# ambisoniqueAlim.net
KiCad netlist of a schematic drawn in EAGLE
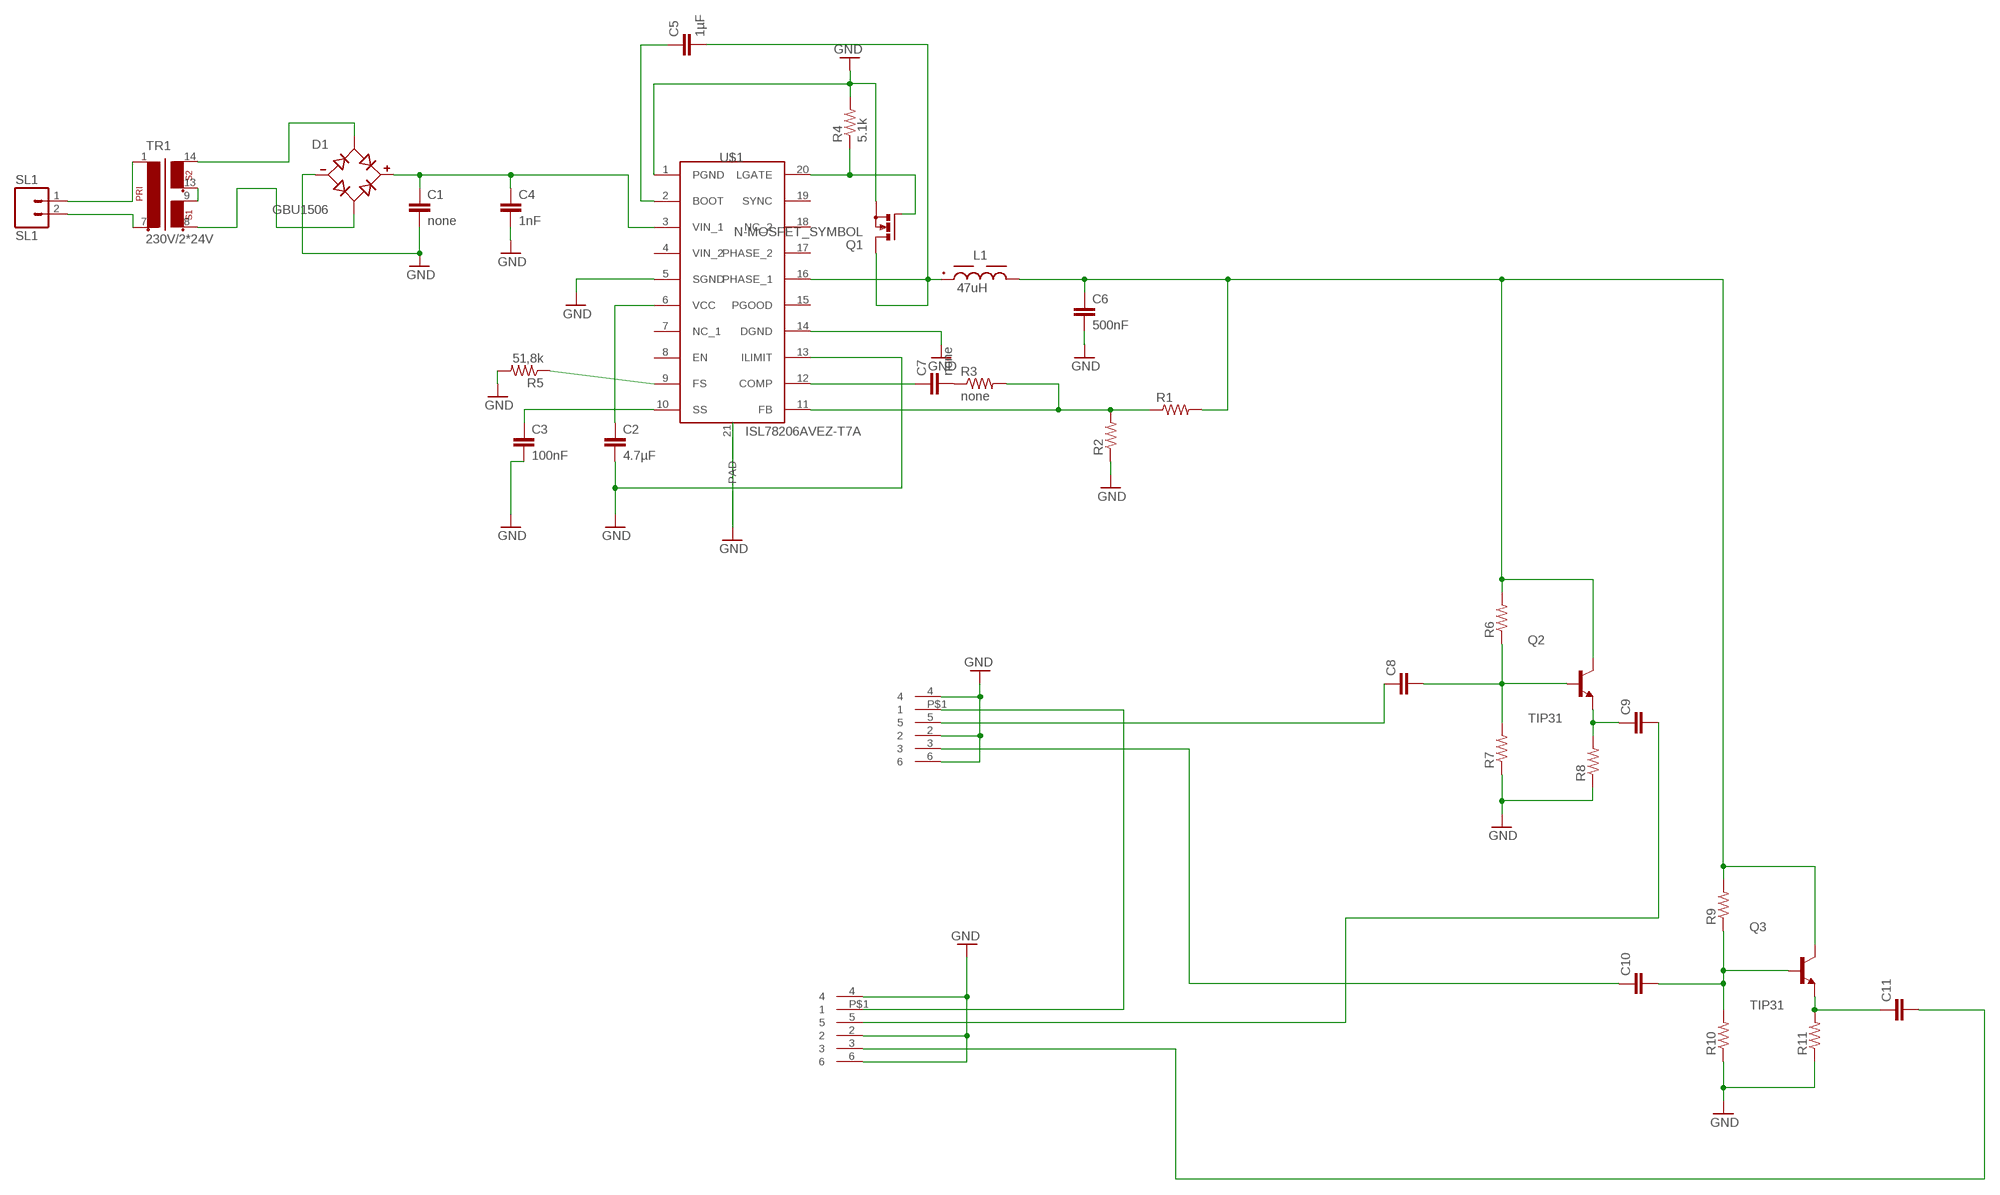
[diagram p0: schematic, sheet 1]

(export (version "E")
  (design (tool "Eeschema 10.0.6"))
  (components
    (comp (ref "C1")
      (value "none")
      (footprint "eagle-import:C0603")
      (libsource (lib "eagle-import") (part "C-EUC0603"))
    )
    (comp (ref "C2")
      (value "4.7µF")
      (footprint "eagle-import:C0603")
      (libsource (lib "eagle-import") (part "C-EUC0603"))
    )
    (comp (ref "C3")
      (value "100nF")
      (footprint "eagle-import:C0603")
      (libsource (lib "eagle-import") (part "C-EUC0603"))
    )
    (comp (ref "C4")
      (value "1nF")
      (footprint "eagle-import:C0603")
      (libsource (lib "eagle-import") (part "C-EUC0603"))
    )
    (comp (ref "C5")
      (value "1µF")
      (footprint "eagle-import:C0603")
      (libsource (lib "eagle-import") (part "C-EUC0603"))
    )
    (comp (ref "C6")
      (value "500nF")
      (footprint "eagle-import:C0603")
      (libsource (lib "eagle-import") (part "C-EUC0603"))
    )
    (comp (ref "C7")
      (value "none")
      (footprint "eagle-import:C0603")
      (libsource (lib "eagle-import") (part "C-EUC0603"))
    )
    (comp (ref "C8")
      (value "C-EUC0603")
      (footprint "eagle-import:C0603")
      (libsource (lib "eagle-import") (part "C-EUC0603"))
    )
    (comp (ref "C9")
      (value "C-EUC0603")
      (footprint "eagle-import:C0603")
      (libsource (lib "eagle-import") (part "C-EUC0603"))
    )
    (comp (ref "C10")
      (value "C-EUC0603")
      (footprint "eagle-import:C0603")
      (libsource (lib "eagle-import") (part "C-EUC0603"))
    )
    (comp (ref "C11")
      (value "C-EUC0603")
      (footprint "eagle-import:C0603")
      (libsource (lib "eagle-import") (part "C-EUC0603"))
    )
    (comp (ref "D1")
      (value "GBU1506")
      (footprint "eagle-import:SIP343W114P508L2205H2134Q4")
      (fields (field (name "MF") "Taiwan Semiconductor Corporation"))
      (libsource (lib "eagle-import") (part "GBU1506"))
    )
    (comp (ref "L1")
      (value "47uH")
      (footprint "eagle-import:WE-PDA_1210")
      (libsource (lib "eagle-import") (part "WE-PDA_1210_7847709470"))
    )
    (comp (ref "Q2")
      (value "TIP31")
      (footprint "eagle-import:TO254P1060X482X2222-3")
      (fields (field (name "MF") "ON"))
      (libsource (lib "eagle-import") (part "TIP31"))
    )
    (comp (ref "Q3")
      (value "TIP31")
      (footprint "eagle-import:TO254P1060X482X2222-3")
      (fields (field (name "MF") "ON"))
      (libsource (lib "eagle-import") (part "TIP31"))
    )
    (comp (ref "R1")
      (value "R-US_R0603")
      (footprint "eagle-import:R0603")
      (libsource (lib "eagle-import") (part "R-US_R0603"))
    )
    (comp (ref "R2")
      (value "R-US_R0603")
      (footprint "eagle-import:R0603")
      (libsource (lib "eagle-import") (part "R-US_R0603"))
    )
    (comp (ref "R3")
      (value "none")
      (footprint "eagle-import:R0603")
      (libsource (lib "eagle-import") (part "R-US_R0603"))
    )
    (comp (ref "R4")
      (value "5.1k")
      (footprint "eagle-import:R0603")
      (libsource (lib "eagle-import") (part "R-US_R0603"))
    )
    (comp (ref "R5")
      (value "51,8k")
      (footprint "eagle-import:R0603")
      (libsource (lib "eagle-import") (part "R-US_R0603"))
    )
    (comp (ref "R6")
      (value "R-US_R0603")
      (footprint "eagle-import:R0603")
      (libsource (lib "eagle-import") (part "R-US_R0603"))
    )
    (comp (ref "R7")
      (value "R-US_R0603")
      (footprint "eagle-import:R0603")
      (libsource (lib "eagle-import") (part "R-US_R0603"))
    )
    (comp (ref "R8")
      (value "R-US_R0603")
      (footprint "eagle-import:R0603")
      (libsource (lib "eagle-import") (part "R-US_R0603"))
    )
    (comp (ref "R9")
      (value "R-US_R0603")
      (footprint "eagle-import:R0603")
      (libsource (lib "eagle-import") (part "R-US_R0603"))
    )
    (comp (ref "R10")
      (value "R-US_R0603")
      (footprint "eagle-import:R0603")
      (libsource (lib "eagle-import") (part "R-US_R0603"))
    )
    (comp (ref "R11")
      (value "R-US_R0603")
      (footprint "eagle-import:R0603")
      (libsource (lib "eagle-import") (part "R-US_R0603"))
    )
    (comp (ref "SL1")
      (value "SL1")
      (footprint "eagle-import:02P")
      (libsource (lib "eagle-import") (part "M02"))
    )
    (comp (ref "TR1")
      (value "230V/2*24V")
      (footprint "eagle-import:EI60-2")
      (libsource (lib "eagle-import") (part "EI60-2"))
    )
    (comp (ref "U$1")
      (value "ISL78206AVEZ-T7A")
      (footprint "eagle-import:SOP65P640X110-21N")
      (libsource (lib "eagle-import") (part "ISL78206AVEZ-T7A"))
    )
    (comp (ref "U$2")
      (value "JACK6.35MMRSPRODEV")
      (footprint "eagle-import:JACKRSPRO6.35MM")
      (libsource (lib "eagle-import") (part "JACK6.35MMRSPRODEV"))
    )
    (comp (ref "U$3")
      (value "JACK6.35MMRSPRODEV")
      (footprint "eagle-import:JACKRSPRO6.35MM")
      (libsource (lib "eagle-import") (part "JACK6.35MMRSPRODEV"))
    )
  )
  (nets
    (net (code "1") (name "GND") (class "Default")
      (node (ref "C1") (pin "2") (pinfunction "2_2") (pintype "passive"))
      (node (ref "C2") (pin "2") (pinfunction "2_2") (pintype "passive"))
      (node (ref "C3") (pin "2") (pinfunction "2_2") (pintype "passive"))
      (node (ref "C4") (pin "2") (pinfunction "2_2") (pintype "passive"))
      (node (ref "C6") (pin "2") (pinfunction "2_2") (pintype "passive"))
      (node (ref "D1") (pin "-") (pinfunction "-_-") (pintype "passive"))
      (node (ref "R10") (pin "1") (pinfunction "1_1") (pintype "passive"))
      (node (ref "R11") (pin "1") (pinfunction "1_1") (pintype "passive"))
      (node (ref "R2") (pin "1") (pinfunction "1_1") (pintype "passive"))
      (node (ref "R4") (pin "2") (pinfunction "2_2") (pintype "passive"))
      (node (ref "R5") (pin "2") (pinfunction "2_2") (pintype "passive"))
      (node (ref "R7") (pin "1") (pinfunction "1_1") (pintype "passive"))
      (node (ref "R8") (pin "1") (pinfunction "1_1") (pintype "passive"))
      (node (ref "U$1") (pin "1") (pinfunction "PGND_1") (pintype "bidirectional"))
      (node (ref "U$1") (pin "13") (pinfunction "ILIMIT_13") (pintype "bidirectional"))
      (node (ref "U$1") (pin "14") (pinfunction "DGND_14") (pintype "bidirectional"))
      (node (ref "U$1") (pin "21") (pinfunction "PAD_21") (pintype "bidirectional"))
      (node (ref "U$1") (pin "5") (pinfunction "SGND_5") (pintype "bidirectional"))
      (node (ref "U$2") (pin "2") (pinfunction "2_2") (pintype "bidirectional"))
      (node (ref "U$2") (pin "4") (pinfunction "4_4") (pintype "bidirectional"))
      (node (ref "U$2") (pin "6") (pinfunction "6_6") (pintype "bidirectional"))
      (node (ref "U$3") (pin "2") (pinfunction "2_2") (pintype "bidirectional"))
      (node (ref "U$3") (pin "4") (pinfunction "4_4") (pintype "bidirectional"))
      (node (ref "U$3") (pin "6") (pinfunction "6_6") (pintype "bidirectional"))
    )
    (net (code "2") (name "Net-(C7-Pad2)") (class "Default")
      (node (ref "C7") (pin "2") (pinfunction "2_2") (pintype "passive"))
      (node (ref "R3") (pin "1") (pinfunction "1_1") (pintype "passive"))
    )
    (net (code "3") (name "Net-(C8-Pad1)") (class "Default")
      (node (ref "C8") (pin "1") (pinfunction "1_1") (pintype "passive"))
      (node (ref "U$2") (pin "5") (pinfunction "5_5") (pintype "bidirectional"))
    )
    (net (code "4") (name "Net-(C9-Pad2)") (class "Default")
      (node (ref "C9") (pin "2") (pinfunction "2_2") (pintype "passive"))
      (node (ref "U$3") (pin "5") (pinfunction "5_5") (pintype "bidirectional"))
    )
    (net (code "5") (name "Net-(C10-Pad1)") (class "Default")
      (node (ref "C10") (pin "1") (pinfunction "1_1") (pintype "passive"))
      (node (ref "U$2") (pin "3") (pinfunction "3_3") (pintype "bidirectional"))
    )
    (net (code "6") (name "Net-(C11-Pad2)") (class "Default")
      (node (ref "C11") (pin "2") (pinfunction "2_2") (pintype "passive"))
      (node (ref "U$3") (pin "3") (pinfunction "3_3") (pintype "bidirectional"))
    )
    (net (code "7") (name "Net-(Q2-B)") (class "Default")
      (node (ref "C8") (pin "2") (pinfunction "2_2") (pintype "passive"))
      (node (ref "Q2") (pin "1") (pinfunction "B_1") (pintype "passive"))
      (node (ref "R6") (pin "1") (pinfunction "1_1") (pintype "passive"))
      (node (ref "R7") (pin "2") (pinfunction "2_2") (pintype "passive"))
    )
    (net (code "8") (name "Net-(Q2-C)") (class "Default")
      (node (ref "C6") (pin "1") (pinfunction "1_1") (pintype "passive"))
      (node (ref "L1") (pin "2") (pinfunction "2_2") (pintype "passive"))
      (node (ref "Q2") (pin "2") (pinfunction "C_2") (pintype "passive"))
      (node (ref "Q3") (pin "2") (pinfunction "C_2") (pintype "passive"))
      (node (ref "R1") (pin "2") (pinfunction "2_2") (pintype "passive"))
      (node (ref "R6") (pin "2") (pinfunction "2_2") (pintype "passive"))
      (node (ref "R9") (pin "2") (pinfunction "2_2") (pintype "passive"))
    )
    (net (code "9") (name "Net-(Q2-E)") (class "Default")
      (node (ref "C9") (pin "1") (pinfunction "1_1") (pintype "passive"))
      (node (ref "Q2") (pin "3") (pinfunction "E_3") (pintype "passive"))
      (node (ref "R8") (pin "2") (pinfunction "2_2") (pintype "passive"))
    )
    (net (code "10") (name "Net-(Q3-B)") (class "Default")
      (node (ref "C10") (pin "2") (pinfunction "2_2") (pintype "passive"))
      (node (ref "Q3") (pin "1") (pinfunction "B_1") (pintype "passive"))
      (node (ref "R10") (pin "2") (pinfunction "2_2") (pintype "passive"))
      (node (ref "R9") (pin "1") (pinfunction "1_1") (pintype "passive"))
    )
    (net (code "11") (name "Net-(Q3-E)") (class "Default")
      (node (ref "C11") (pin "1") (pinfunction "1_1") (pintype "passive"))
      (node (ref "Q3") (pin "3") (pinfunction "E_3") (pintype "passive"))
      (node (ref "R11") (pin "2") (pinfunction "2_2") (pintype "passive"))
    )
    (net (code "12") (name "Net-(SL1-Pad1)") (class "Default")
      (node (ref "SL1") (pin "1") (pinfunction "1_1") (pintype "passive"))
      (node (ref "TR1") (pin "1") (pinfunction "1_1") (pintype "passive"))
    )
    (net (code "13") (name "Net-(TR1-2)") (class "Default")
      (node (ref "SL1") (pin "2") (pinfunction "2_2") (pintype "passive"))
      (node (ref "TR1") (pin "7") (pinfunction "2_7") (pintype "passive"))
    )
    (net (code "14") (name "Net-(TR1-3)") (class "Default")
      (node (ref "D1") (pin "AC2") (pinfunction "AC2_AC2") (pintype "passive"))
      (node (ref "TR1") (pin "8") (pinfunction "3_8") (pintype "passive"))
    )
    (net (code "15") (name "Net-(TR1-4)") (class "Default")
      (node (ref "TR1") (pin "13") (pinfunction "5_13") (pintype "passive"))
      (node (ref "TR1") (pin "9") (pinfunction "4_9") (pintype "passive"))
    )
    (net (code "16") (name "Net-(TR1-6)") (class "Default")
      (node (ref "D1") (pin "AC1") (pinfunction "AC1_AC1") (pintype "passive"))
      (node (ref "TR1") (pin "14") (pinfunction "6_14") (pintype "passive"))
    )
    (net (code "17") (name "Net-(U$1-BOOT)") (class "Default")
      (node (ref "C5") (pin "1") (pinfunction "1_1") (pintype "passive"))
      (node (ref "U$1") (pin "2") (pinfunction "BOOT_2") (pintype "bidirectional"))
    )
    (net (code "18") (name "Net-(U$1-COMP)") (class "Default")
      (node (ref "C7") (pin "1") (pinfunction "1_1") (pintype "passive"))
      (node (ref "U$1") (pin "12") (pinfunction "COMP_12") (pintype "bidirectional"))
    )
    (net (code "19") (name "Net-(U$1-FB)") (class "Default")
      (node (ref "R1") (pin "1") (pinfunction "1_1") (pintype "passive"))
      (node (ref "R2") (pin "2") (pinfunction "2_2") (pintype "passive"))
      (node (ref "R3") (pin "2") (pinfunction "2_2") (pintype "passive"))
      (node (ref "U$1") (pin "11") (pinfunction "FB_11") (pintype "bidirectional"))
    )
    (net (code "20") (name "Net-(U$1-FS)") (class "Default")
      (node (ref "R5") (pin "1") (pinfunction "1_1") (pintype "passive"))
      (node (ref "U$1") (pin "9") (pinfunction "FS_9") (pintype "bidirectional"))
    )
    (net (code "21") (name "Net-(U$1-LGATE)") (class "Default")
      (node (ref "R4") (pin "1") (pinfunction "1_1") (pintype "passive"))
      (node (ref "U$1") (pin "20") (pinfunction "LGATE_20") (pintype "bidirectional"))
    )
    (net (code "22") (name "Net-(U$1-PHASE_1)") (class "Default")
      (node (ref "C5") (pin "2") (pinfunction "2_2") (pintype "passive"))
      (node (ref "L1") (pin "1") (pinfunction "1_1") (pintype "passive"))
      (node (ref "U$1") (pin "16") (pinfunction "PHASE_1_16") (pintype "bidirectional"))
    )
    (net (code "23") (name "Net-(U$1-SS)") (class "Default")
      (node (ref "C3") (pin "1") (pinfunction "1_1") (pintype "passive"))
      (node (ref "U$1") (pin "10") (pinfunction "SS_10") (pintype "bidirectional"))
    )
    (net (code "24") (name "Net-(U$1-VCC)") (class "Default")
      (node (ref "C2") (pin "1") (pinfunction "1_1") (pintype "passive"))
      (node (ref "U$1") (pin "6") (pinfunction "VCC_6") (pintype "bidirectional"))
    )
    (net (code "25") (name "Net-(U$1-VIN_1)") (class "Default")
      (node (ref "C1") (pin "1") (pinfunction "1_1") (pintype "passive"))
      (node (ref "C4") (pin "1") (pinfunction "1_1") (pintype "passive"))
      (node (ref "D1") (pin "+") (pinfunction "+_+") (pintype "passive"))
      (node (ref "U$1") (pin "3") (pinfunction "VIN_1_3") (pintype "bidirectional"))
    )
    (net (code "26") (name "Net-(U$2-1)") (class "Default")
      (node (ref "U$2") (pin "P$1") (pinfunction "1_P$1") (pintype "bidirectional"))
      (node (ref "U$3") (pin "P$1") (pinfunction "1_P$1") (pintype "bidirectional"))
    )
    (net (code "27") (name "unconnected-(U$1-EN-Pad8)") (class "Default")
      (node (ref "U$1") (pin "8") (pinfunction "EN_8") (pintype "bidirectional"))
    )
    (net (code "28") (name "unconnected-(U$1-NC_1-Pad7)") (class "Default")
      (node (ref "U$1") (pin "7") (pinfunction "NC_1_7") (pintype "bidirectional"))
    )
    (net (code "29") (name "unconnected-(U$1-NC_2-Pad18)") (class "Default")
      (node (ref "U$1") (pin "18") (pinfunction "NC_2_18") (pintype "bidirectional"))
    )
    (net (code "30") (name "unconnected-(U$1-PGOOD-Pad15)") (class "Default")
      (node (ref "U$1") (pin "15") (pinfunction "PGOOD_15") (pintype "bidirectional"))
    )
    (net (code "31") (name "unconnected-(U$1-PHASE_2-Pad17)") (class "Default")
      (node (ref "U$1") (pin "17") (pinfunction "PHASE_2_17") (pintype "bidirectional"))
    )
    (net (code "32") (name "unconnected-(U$1-SYNC-Pad19)") (class "Default")
      (node (ref "U$1") (pin "19") (pinfunction "SYNC_19") (pintype "bidirectional"))
    )
    (net (code "33") (name "unconnected-(U$1-VIN_2-Pad4)") (class "Default")
      (node (ref "U$1") (pin "4") (pinfunction "VIN_2_4") (pintype "bidirectional"))
    )
  )
)
